# rj45-2x5.net
KiCad netlist of a schematic drawn in EAGLE
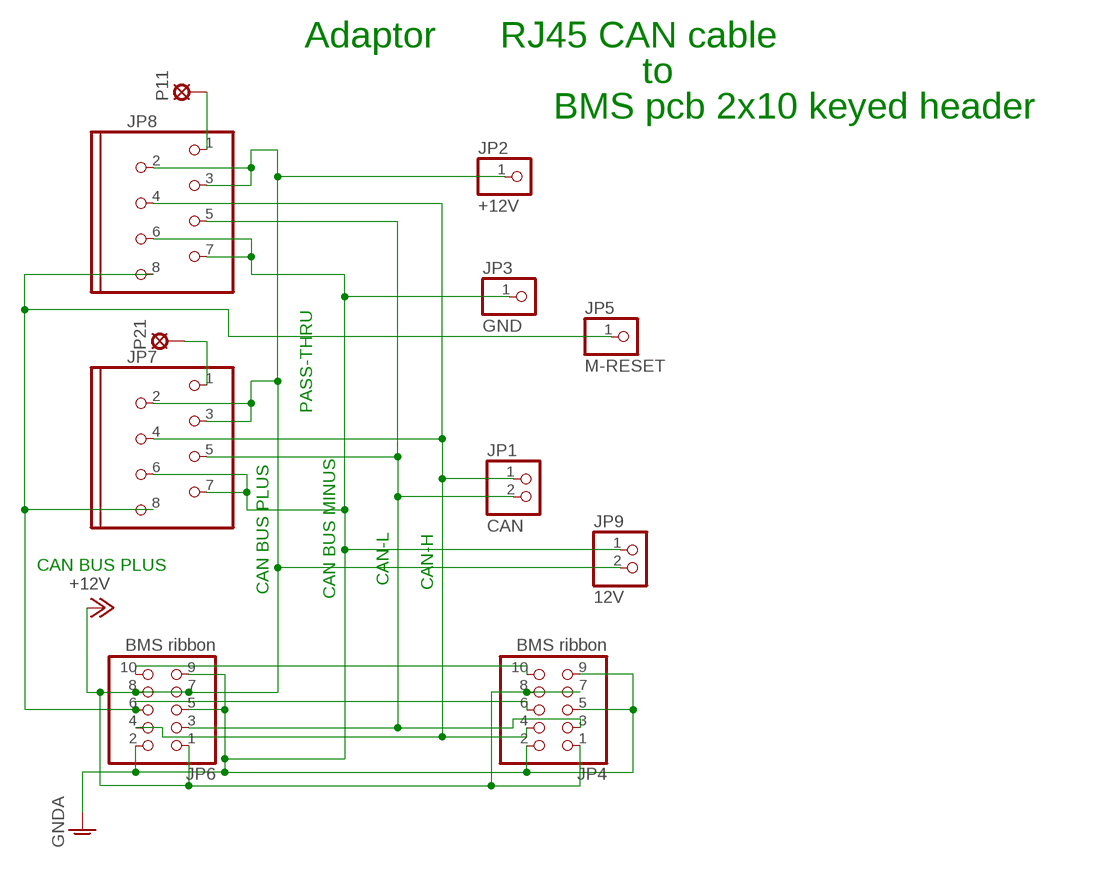
[diagram p0: schematic, sheet 1]

(export (version "E")
  (design (tool "Eeschema 10.0.6"))
  (components
    (comp (ref "JP1")
      (value "CAN")
      (footprint "eagle-import:1X02")
      (libsource (lib "eagle-import") (part "PINHD-1X2"))
    )
    (comp (ref "JP2")
      (value "+12V")
      (footprint "eagle-import:1X01")
      (libsource (lib "eagle-import") (part "PINHD-1X1"))
    )
    (comp (ref "JP3")
      (value "GND")
      (footprint "eagle-import:1X01")
      (libsource (lib "eagle-import") (part "PINHD-1X1"))
    )
    (comp (ref "JP4")
      (value "BMS ribbon")
      (footprint "eagle-import:2X05_KEYED")
      (libsource (lib "eagle-import") (part "PINHD-2X5_KEYED"))
    )
    (comp (ref "JP5")
      (value "M-RESET")
      (footprint "eagle-import:1X01")
      (libsource (lib "eagle-import") (part "PINHD-1X1"))
    )
    (comp (ref "JP6")
      (value "BMS ribbon")
      (footprint "eagle-import:2X05_KEYED")
      (libsource (lib "eagle-import") (part "PINHD-2X5_KEYED"))
    )
    (comp (ref "JP7")
      (value "MOD8P8C")
      (footprint "eagle-import:MOD8P8C")
      (libsource (lib "eagle-import") (part "MOD8P8C"))
    )
    (comp (ref "JP8")
      (value "MOD8P8C")
      (footprint "eagle-import:MOD8P8C")
      (libsource (lib "eagle-import") (part "MOD8P8C"))
    )
    (comp (ref "JP9")
      (value "12V")
      (footprint "eagle-import:1X02")
      (libsource (lib "eagle-import") (part "PINHD-1X2"))
    )
    (comp (ref "P11")
      (value "SOLPAD035")
      (footprint "eagle-import:SOLDPAD035")
      (libsource (lib "eagle-import") (part "SOLPAD035"))
    )
    (comp (ref "P21")
      (value "SOLPAD035")
      (footprint "eagle-import:SOLDPAD035")
      (libsource (lib "eagle-import") (part "SOLPAD035"))
    )
  )
  (nets
    (net (code "1") (name "+12V") (class "Default")
      (node (ref "JP2") (pin "1") (pinfunction "1_1") (pintype "passive"))
      (node (ref "JP4") (pin "1") (pinfunction "1_1") (pintype "passive"))
      (node (ref "JP4") (pin "7") (pinfunction "7_7") (pintype "passive"))
      (node (ref "JP4") (pin "8") (pinfunction "8_8") (pintype "passive"))
      (node (ref "JP6") (pin "1") (pinfunction "1_1") (pintype "passive"))
      (node (ref "JP6") (pin "7") (pinfunction "7_7") (pintype "passive"))
      (node (ref "JP6") (pin "8") (pinfunction "8_8") (pintype "passive"))
      (node (ref "JP7") (pin "2") (pinfunction "5_2") (pintype "passive"))
      (node (ref "JP7") (pin "3") (pinfunction "2_3") (pintype "passive"))
      (node (ref "JP8") (pin "2") (pinfunction "5_2") (pintype "passive"))
      (node (ref "JP8") (pin "3") (pinfunction "2_3") (pintype "passive"))
      (node (ref "JP9") (pin "2") (pinfunction "2_2") (pintype "passive"))
    )
    (net (code "2") (name "GNDA") (class "Default")
      (node (ref "JP3") (pin "1") (pinfunction "1_1") (pintype "passive"))
      (node (ref "JP4") (pin "2") (pinfunction "2_2") (pintype "passive"))
      (node (ref "JP4") (pin "5") (pinfunction "5_5") (pintype "passive"))
      (node (ref "JP4") (pin "9") (pinfunction "9_9") (pintype "passive"))
      (node (ref "JP6") (pin "2") (pinfunction "2_2") (pintype "passive"))
      (node (ref "JP6") (pin "5") (pinfunction "5_5") (pintype "passive"))
      (node (ref "JP6") (pin "9") (pinfunction "9_9") (pintype "passive"))
      (node (ref "JP7") (pin "6") (pinfunction "7_6") (pintype "passive"))
      (node (ref "JP7") (pin "7") (pinfunction "4_7") (pintype "passive"))
      (node (ref "JP8") (pin "6") (pinfunction "7_6") (pintype "passive"))
      (node (ref "JP8") (pin "7") (pinfunction "4_7") (pintype "passive"))
      (node (ref "JP9") (pin "1") (pinfunction "1_1") (pintype "passive"))
    )
    (net (code "3") (name "Net-(JP4-Pad6)") (class "Default")
      (node (ref "JP4") (pin "6") (pinfunction "6_6") (pintype "passive"))
      (node (ref "JP5") (pin "1") (pinfunction "1_1") (pintype "passive"))
      (node (ref "JP6") (pin "6") (pinfunction "6_6") (pintype "passive"))
      (node (ref "JP7") (pin "8") (pinfunction "8_8") (pintype "passive"))
      (node (ref "JP8") (pin "8") (pinfunction "8_8") (pintype "passive"))
    )
    (net (code "4") (name "Net-(JP4-Pad10)") (class "Default")
      (node (ref "JP4") (pin "10") (pinfunction "10_10") (pintype "passive"))
      (node (ref "JP6") (pin "10") (pinfunction "10_10") (pintype "passive"))
    )
    (net (code "5") (name "Net-(JP7-3)") (class "Default")
      (node (ref "JP1") (pin "2") (pinfunction "2_2") (pintype "passive"))
      (node (ref "JP4") (pin "3") (pinfunction "3_3") (pintype "passive"))
      (node (ref "JP6") (pin "3") (pinfunction "3_3") (pintype "passive"))
      (node (ref "JP7") (pin "5") (pinfunction "3_5") (pintype "passive"))
      (node (ref "JP8") (pin "5") (pinfunction "3_5") (pintype "passive"))
    )
    (net (code "6") (name "Net-(JP7-6)") (class "Default")
      (node (ref "JP1") (pin "1") (pinfunction "1_1") (pintype "passive"))
      (node (ref "JP4") (pin "4") (pinfunction "4_4") (pintype "passive"))
      (node (ref "JP6") (pin "4") (pinfunction "4_4") (pintype "passive"))
      (node (ref "JP7") (pin "4") (pinfunction "6_4") (pintype "passive"))
      (node (ref "JP8") (pin "4") (pinfunction "6_4") (pintype "passive"))
    )
    (net (code "7") (name "Net-(JP7-Pad1)") (class "Default")
      (node (ref "JP7") (pin "1") (pinfunction "1_1") (pintype "passive"))
      (node (ref "P21") (pin "MP") (pinfunction "MP_MP") (pintype "passive"))
    )
    (net (code "8") (name "Net-(JP8-Pad1)") (class "Default")
      (node (ref "JP8") (pin "1") (pinfunction "1_1") (pintype "passive"))
      (node (ref "P11") (pin "MP") (pinfunction "MP_MP") (pintype "passive"))
    )
  )
)
